# LB_BIT_o4_VIBRATIONMOTOR-v02_rev1.net
KiCad netlist of a schematic drawn in EAGLE
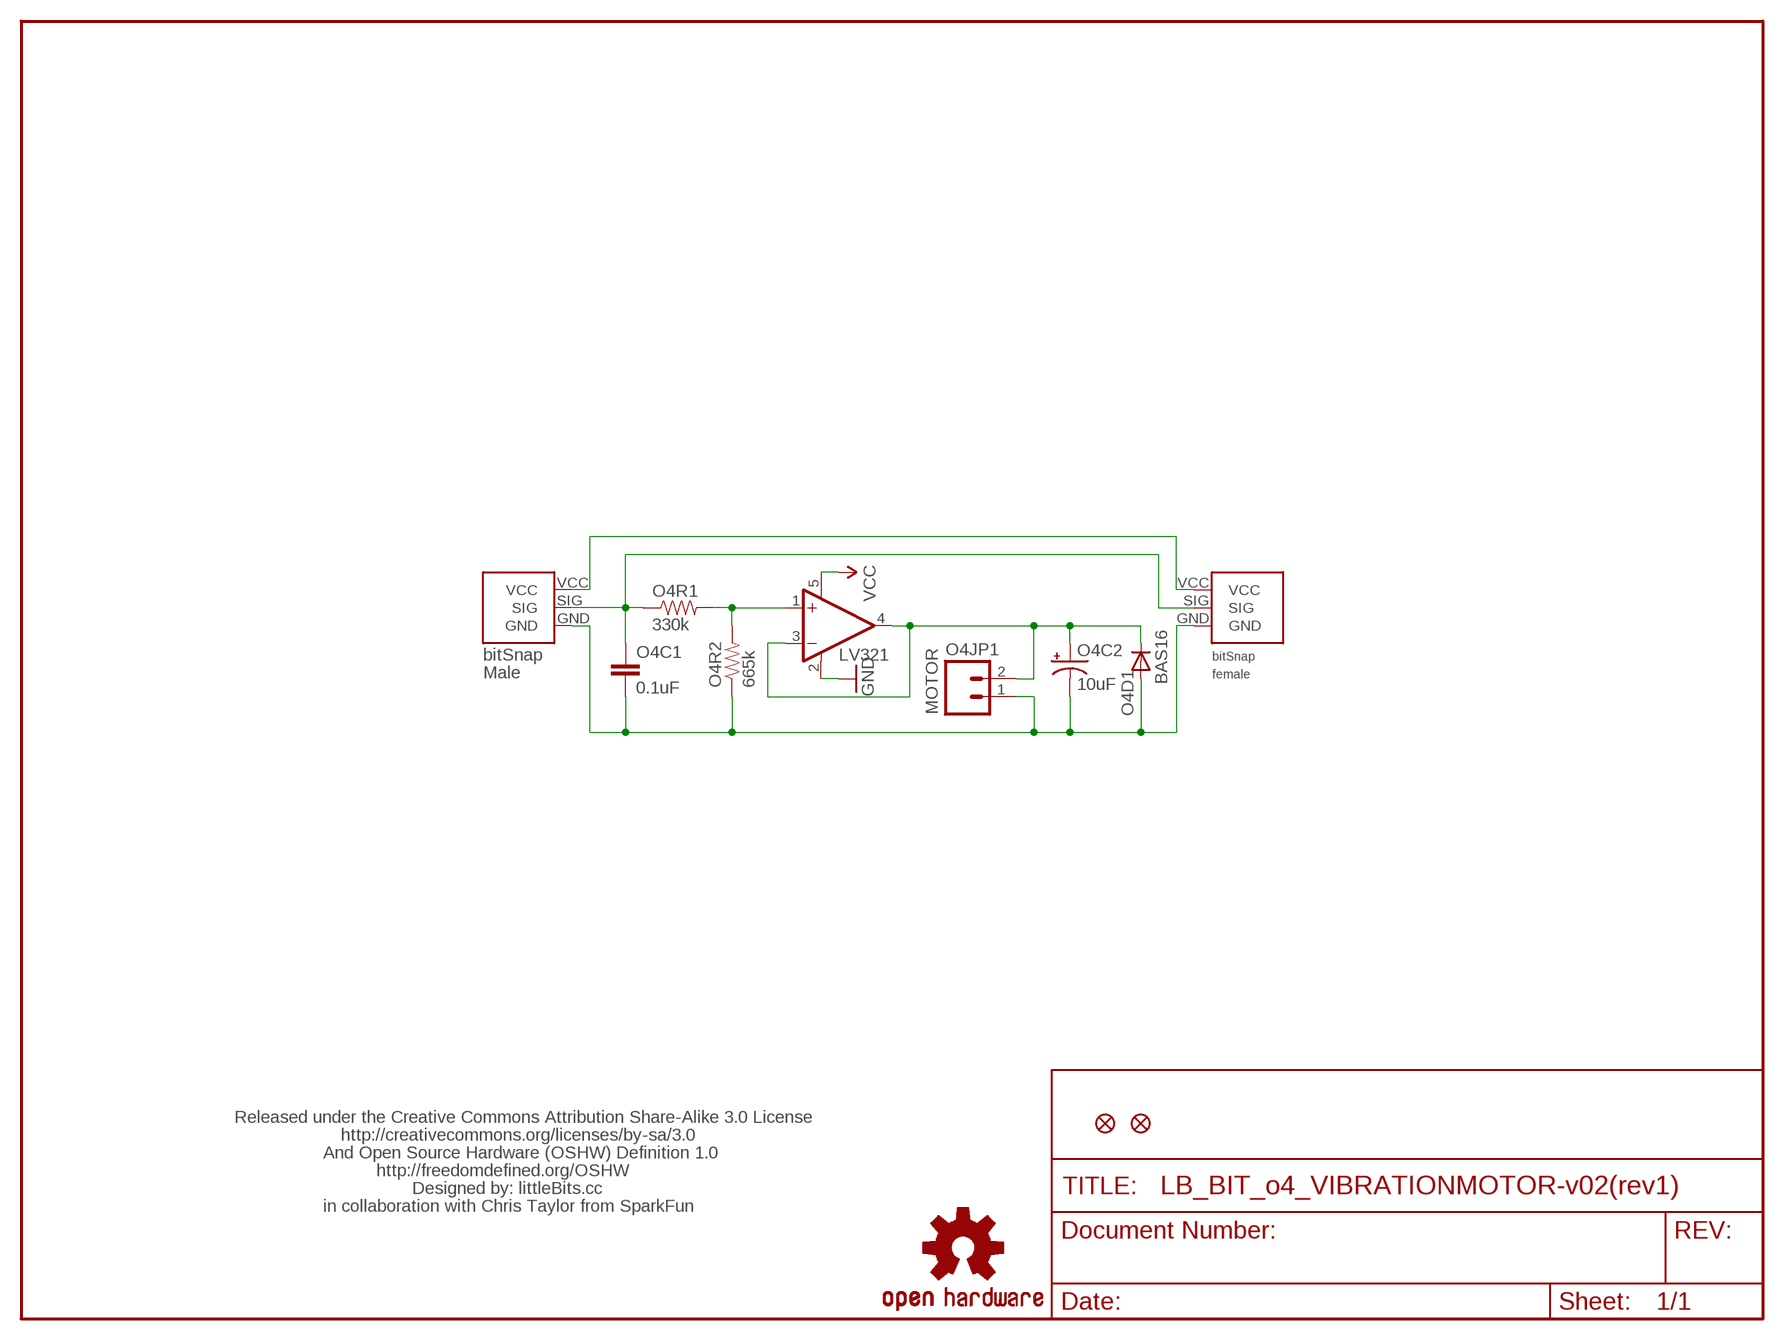
[diagram p0: schematic, sheet 1]

(export (version "E")
  (design (tool "Eeschema 10.0.6"))
  (components
    (comp (ref "JP2")
      (value "FIDUCIAL1X2.5")
      (footprint "eagle-import:FIDUCIAL-1X2.5")
      (libsource (lib "eagle-import") (part "FIDUCIAL1X2.5"))
    )
    (comp (ref "JP3")
      (value "FIDUCIAL1X2.5")
      (footprint "eagle-import:FIDUCIAL-1X2.5")
      (libsource (lib "eagle-import") (part "FIDUCIAL1X2.5"))
    )
    (comp (ref "O4BSF")
      (value "BITSNAP_FEMALE")
      (footprint "eagle-import:BITSNAP_FEMALE")
      (libsource (lib "eagle-import") (part "BITSNAP_FEMALE"))
    )
    (comp (ref "O4BSM")
      (value "BITSNAP_MALE")
      (footprint "eagle-import:BITSNAP_MALE")
      (libsource (lib "eagle-import") (part "BITSNAP_MALE"))
    )
    (comp (ref "O4C1")
      (value "0.1uF")
      (footprint "eagle-import:0603-CAP")
      (libsource (lib "eagle-import") (part "CAP0603-CAP"))
    )
    (comp (ref "O4C2")
      (value "10uF")
      (footprint "eagle-import:EIA3216")
      (libsource (lib "eagle-import") (part "CAP_POL1206"))
    )
    (comp (ref "O4D1")
      (value "BAS16")
      (footprint "eagle-import:SOT23-3")
      (libsource (lib "eagle-import") (part "DIODESOT23"))
    )
    (comp (ref "O4JP1")
      (value "MOTOR")
      (footprint "eagle-import:1X02")
      (libsource (lib "eagle-import") (part "M02PTH"))
    )
    (comp (ref "O4R1")
      (value "330k")
      (footprint "eagle-import:0603-RES")
      (libsource (lib "eagle-import") (part "RESISTOR0603-RES"))
    )
    (comp (ref "O4R2")
      (value "665k")
      (footprint "eagle-import:0603-RES")
      (libsource (lib "eagle-import") (part "RESISTOR0603-RES"))
    )
    (comp (ref "O4U1")
      (value "LV321")
      (footprint "eagle-import:SC70")
      (libsource (lib "eagle-import") (part "LV321"))
    )
    (comp (ref "U$1")
      (value "LB_CREDITS")
      (footprint "eagle-import:OSHWCREDIT")
      (libsource (lib "eagle-import") (part "LB_CREDITS"))
    )
    (comp (ref "U$5")
      (value "OSHW-LOGOL")
      (footprint "eagle-import:OSHW-LOGO-L")
      (libsource (lib "eagle-import") (part "OSHW-LOGOL"))
    )
  )
  (nets
    (net (code "1") (name "GND") (class "Default")
      (node (ref "O4BSF") (pin "GND") (pinfunction "GND_GND") (pintype "bidirectional"))
      (node (ref "O4BSM") (pin "GND") (pinfunction "GND_GND") (pintype "bidirectional"))
      (node (ref "O4C1") (pin "2") (pinfunction "2_2") (pintype "passive"))
      (node (ref "O4C2") (pin "C") (pinfunction "-_C") (pintype "passive"))
      (node (ref "O4D1") (pin "1") (pinfunction "A_1") (pintype "passive"))
      (node (ref "O4JP1") (pin "1") (pinfunction "1_1") (pintype "passive"))
      (node (ref "O4R2") (pin "1") (pinfunction "1_1") (pintype "passive"))
      (node (ref "O4U1") (pin "2") (pinfunction "V-_2") (pintype "power_in"))
    )
    (net (code "2") (name "Net-(O4BSF-PadSIG)") (class "Default")
      (node (ref "O4BSF") (pin "SIG") (pinfunction "SIG_SIG") (pintype "bidirectional"))
      (node (ref "O4BSM") (pin "SIG") (pinfunction "SIG_SIG") (pintype "bidirectional"))
      (node (ref "O4C1") (pin "1") (pinfunction "1_1") (pintype "passive"))
      (node (ref "O4R1") (pin "1") (pinfunction "1_1") (pintype "passive"))
    )
    (net (code "3") (name "Net-(O4C2-+)") (class "Default")
      (node (ref "O4C2") (pin "A") (pinfunction "+_A") (pintype "passive"))
      (node (ref "O4D1") (pin "3") (pinfunction "C_3") (pintype "passive"))
      (node (ref "O4JP1") (pin "2") (pinfunction "2_2") (pintype "passive"))
      (node (ref "O4U1") (pin "3") (pinfunction "-IN_3") (pintype "input"))
      (node (ref "O4U1") (pin "4") (pinfunction "OUT_4") (pintype "output"))
    )
    (net (code "4") (name "Net-(O4U1-+IN)") (class "Default")
      (node (ref "O4R1") (pin "2") (pinfunction "2_2") (pintype "passive"))
      (node (ref "O4R2") (pin "2") (pinfunction "2_2") (pintype "passive"))
      (node (ref "O4U1") (pin "1") (pinfunction "+IN_1") (pintype "input"))
    )
    (net (code "5") (name "VCC") (class "Default")
      (node (ref "O4BSF") (pin "VCC") (pinfunction "VCC_VCC") (pintype "bidirectional"))
      (node (ref "O4BSM") (pin "VCC") (pinfunction "VCC_VCC") (pintype "bidirectional"))
      (node (ref "O4U1") (pin "5") (pinfunction "V+_5") (pintype "power_in"))
    )
  )
)
